# Gas_Analyser_O2_CO2.net
KiCad netlist of a schematic drawn in Altium Designer
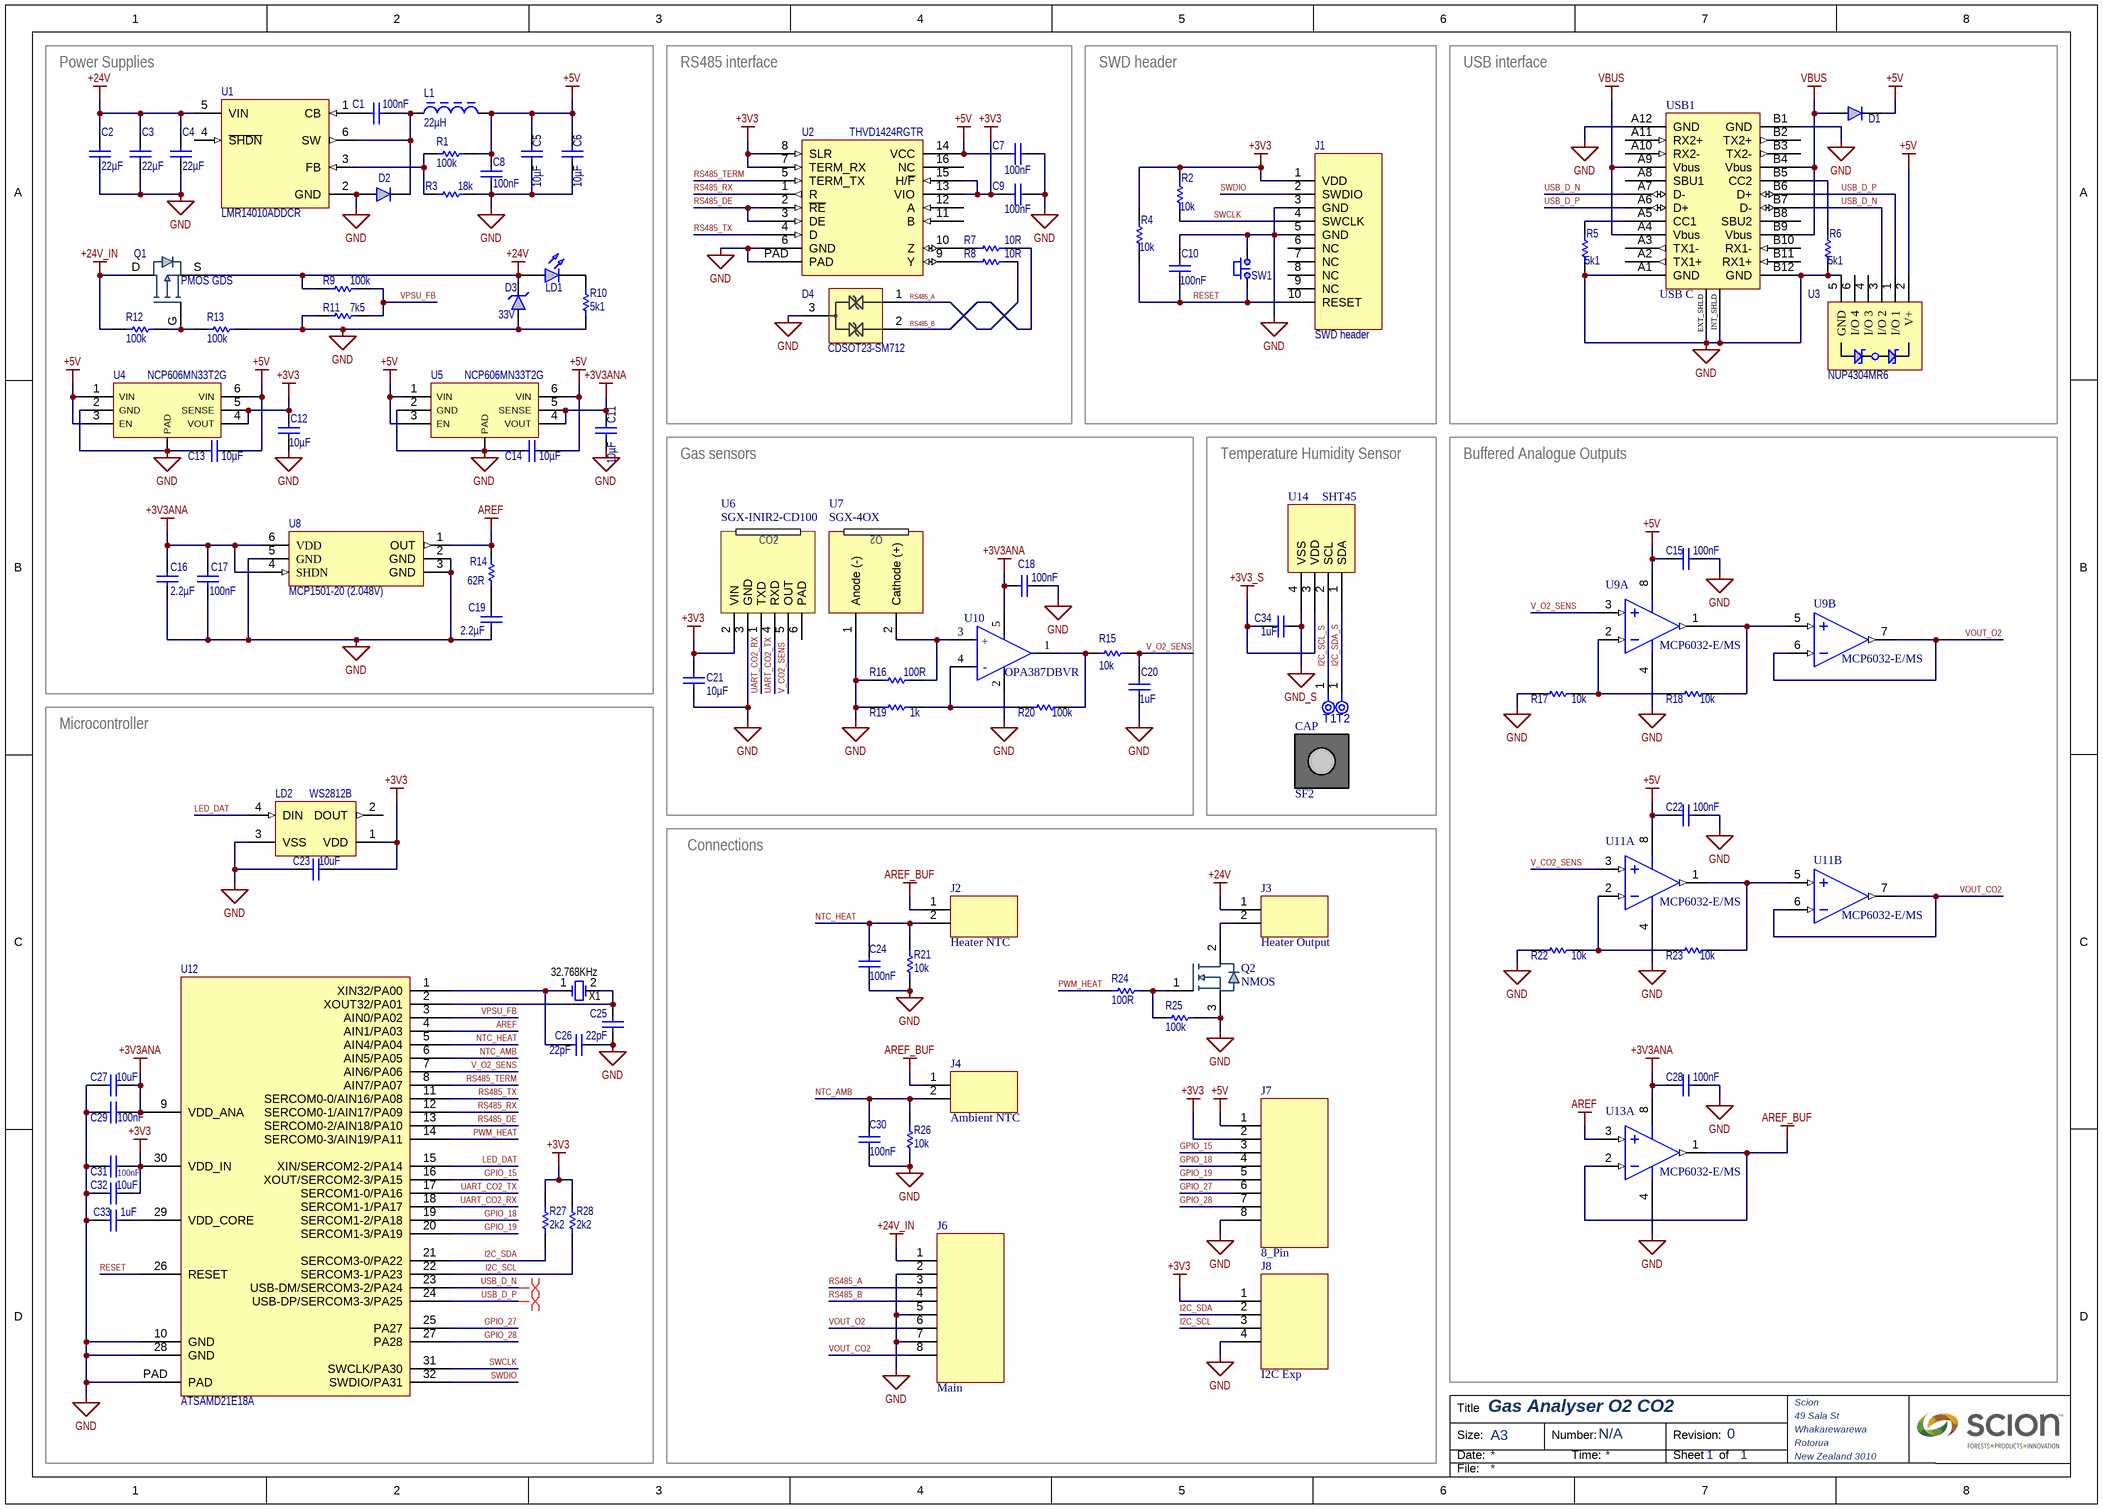
[diagram p0: Gas Analyser O2 CO2.SchDoc]

(export (version "E")
  (design (tool "Eeschema 10.0.6"))
  (components
    (comp (ref "C1")
      (value "100nF")
      (footprint "0603_CAP")
      (description "SMD Capacitor")
      (fields (field (name "Comment") "Capacitor"))
      (libsource (lib "Scion Research") (part "CMP-019-00005-2"))
    )
    (comp (ref "C2")
      (value "22µF")
      (footprint "1206_CAP")
      (description "SMD Capacitor")
      (fields (field (name "Comment") "Capacitor"))
      (libsource (lib "Scion Research") (part "CMP-019-00005-2"))
    )
    (comp (ref "C3")
      (value "22µF")
      (footprint "1206_CAP")
      (description "SMD Capacitor")
      (fields (field (name "Comment") "Capacitor"))
      (libsource (lib "Scion Research") (part "CMP-019-00005-2"))
    )
    (comp (ref "C4")
      (value "22µF")
      (footprint "1206_CAP")
      (description "SMD Capacitor")
      (fields (field (name "Comment") "Capacitor"))
      (libsource (lib "Scion Research") (part "CMP-019-00005-2"))
    )
    (comp (ref "C5")
      (value "10µF")
      (footprint "0603_CAP")
      (description "SMD Capacitor")
      (fields (field (name "Comment") "Capacitor"))
      (libsource (lib "Scion Research") (part "CMP-019-00005-2"))
    )
    (comp (ref "C6")
      (value "10µF")
      (footprint "0603_CAP")
      (description "SMD Capacitor")
      (fields (field (name "Comment") "Capacitor"))
      (libsource (lib "Scion Research") (part "CMP-019-00005-2"))
    )
    (comp (ref "C7")
      (value "100nF")
      (footprint "0603_CAP")
      (description "SMD Capacitor")
      (fields (field (name "Comment") "Capacitor"))
      (libsource (lib "Scion Research") (part "CMP-019-00005-2"))
    )
    (comp (ref "C8")
      (value "100nF")
      (footprint "0603_CAP")
      (description "SMD Capacitor")
      (fields (field (name "Comment") "Capacitor"))
      (libsource (lib "Scion Research") (part "CMP-019-00005-2"))
    )
    (comp (ref "C9")
      (value "100nF")
      (footprint "0603_CAP")
      (description "SMD Capacitor")
      (fields (field (name "Comment") "Capacitor"))
      (libsource (lib "Scion Research") (part "CMP-019-00005-2"))
    )
    (comp (ref "C10")
      (value "100nF")
      (footprint "0603_CAP")
      (description "SMD Capacitor")
      (fields (field (name "Comment") "Capacitor"))
      (libsource (lib "Scion Research") (part "CMP-019-00005-2"))
    )
    (comp (ref "C11")
      (value "10µF")
      (footprint "0603_CAP")
      (description "SMD Capacitor")
      (fields (field (name "Comment") "Capacitor"))
      (libsource (lib "Scion Research") (part "CMP-019-00005-2"))
    )
    (comp (ref "C12")
      (value "10µF")
      (footprint "0603_CAP")
      (description "SMD Capacitor")
      (fields (field (name "Comment") "Capacitor"))
      (libsource (lib "Scion Research") (part "CMP-019-00005-2"))
    )
    (comp (ref "C13")
      (value "10µF")
      (footprint "0603_CAP")
      (description "SMD Capacitor")
      (fields (field (name "Comment") "Capacitor"))
      (libsource (lib "Scion Research") (part "CMP-019-00005-2"))
    )
    (comp (ref "C14")
      (value "10µF")
      (footprint "0603_CAP")
      (description "SMD Capacitor")
      (fields (field (name "Comment") "Capacitor"))
      (libsource (lib "Scion Research") (part "CMP-019-00005-2"))
    )
    (comp (ref "C15")
      (value "100nF")
      (footprint "0603_CAP")
      (description "SMD Capacitor")
      (fields (field (name "Comment") "Capacitor"))
      (libsource (lib "Scion Research") (part "CMP-019-00005-2"))
    )
    (comp (ref "C16")
      (value "2.2µF")
      (footprint "0603_CAP")
      (description "SMD Capacitor")
      (fields (field (name "Comment") "Capacitor"))
      (libsource (lib "Scion Research") (part "CMP-019-00005-2"))
    )
    (comp (ref "C17")
      (value "100nF")
      (footprint "0603_CAP")
      (description "SMD Capacitor")
      (fields (field (name "Comment") "Capacitor"))
      (libsource (lib "Scion Research") (part "CMP-019-00005-2"))
    )
    (comp (ref "C18")
      (value "100nF")
      (footprint "0603_CAP")
      (description "SMD Capacitor")
      (fields (field (name "Comment") "Capacitor"))
      (libsource (lib "Scion Research") (part "CMP-019-00005-2"))
    )
    (comp (ref "C19")
      (value "2.2µF")
      (footprint "0603_CAP")
      (description "SMD Capacitor")
      (fields (field (name "Comment") "Capacitor"))
      (libsource (lib "Scion Research") (part "CMP-019-00005-2"))
    )
    (comp (ref "C20")
      (value "1uF")
      (footprint "0603_CAP")
      (description "SMD Capacitor")
      (fields (field (name "Comment") "Capacitor"))
      (libsource (lib "Scion Research") (part "CMP-019-00005-2"))
    )
    (comp (ref "C21")
      (value "10µF")
      (footprint "0603_CAP")
      (description "SMD Capacitor")
      (fields (field (name "Comment") "Capacitor"))
      (libsource (lib "Scion Research") (part "CMP-019-00005-2"))
    )
    (comp (ref "C22")
      (value "100nF")
      (footprint "0603_CAP")
      (description "SMD Capacitor")
      (fields (field (name "Comment") "Capacitor"))
      (libsource (lib "Scion Research") (part "CMP-019-00005-2"))
    )
    (comp (ref "C23")
      (value "10uF")
      (footprint "0603_CAP")
      (description "SMD Capacitor")
      (fields (field (name "Comment") "Capacitor"))
      (libsource (lib "Scion Research") (part "CMP-019-00005-2"))
    )
    (comp (ref "C24")
      (value "100nF")
      (footprint "0603_CAP")
      (description "SMD Capacitor")
      (fields (field (name "Comment") "Capacitor"))
      (libsource (lib "Scion Research") (part "CMP-019-00005-2"))
    )
    (comp (ref "C25")
      (value "22pF")
      (footprint "0402_CAP")
      (description "SMD Capacitor")
      (fields (field (name "Comment") "Capacitor"))
      (libsource (lib "Scion Research") (part "CMP-019-00005-2"))
    )
    (comp (ref "C26")
      (value "22pF")
      (footprint "0402_CAP")
      (description "SMD Capacitor")
      (fields (field (name "Comment") "Capacitor"))
      (libsource (lib "Scion Research") (part "CMP-019-00005-2"))
    )
    (comp (ref "C27")
      (value "10uF")
      (footprint "0603_CAP")
      (description "SMD Capacitor")
      (fields (field (name "Comment") "Capacitor"))
      (libsource (lib "Scion Research") (part "CMP-019-00005-2"))
    )
    (comp (ref "C28")
      (value "100nF")
      (footprint "0603_CAP")
      (description "SMD Capacitor")
      (fields (field (name "Comment") "Capacitor"))
      (libsource (lib "Scion Research") (part "CMP-019-00005-2"))
    )
    (comp (ref "C29")
      (value "100nF")
      (footprint "0402_CAP")
      (description "SMD Capacitor")
      (fields (field (name "Comment") "Capacitor"))
      (libsource (lib "Scion Research") (part "CMP-019-00005-2"))
    )
    (comp (ref "C30")
      (value "100nF")
      (footprint "0603_CAP")
      (description "SMD Capacitor")
      (fields (field (name "Comment") "Capacitor"))
      (libsource (lib "Scion Research") (part "CMP-019-00005-2"))
    )
    (comp (ref "C31")
      (value "100nF")
      (footprint "0402_CAP")
      (description "SMD Capacitor")
      (fields (field (name "Comment") "Capacitor"))
      (libsource (lib "Scion Research") (part "CMP-019-00005-2"))
    )
    (comp (ref "C32")
      (value "10uF")
      (footprint "0603_CAP")
      (description "SMD Capacitor")
      (fields (field (name "Comment") "Capacitor"))
      (libsource (lib "Scion Research") (part "CMP-019-00005-2"))
    )
    (comp (ref "C33")
      (value "1uF")
      (footprint "0402_CAP")
      (description "SMD Capacitor")
      (fields (field (name "Comment") "Capacitor"))
      (libsource (lib "Scion Research") (part "CMP-019-00005-2"))
    )
    (comp (ref "C34")
      (value "1uF")
      (footprint "0603_CAP")
      (description "SMD Capacitor")
      (fields (field (name "Comment") "Capacitor"))
      (libsource (lib "Scion Research") (part "CMP-019-00005-2"))
    )
    (comp (ref "CAP")
      (value "SF2")
      (footprint "SF2-Footprint-1")
      (description "Sensirion SHT cap for SHT4x sensors")
      (libsource (lib "Scion Research") (part "SF2-Symbol-1"))
    )
    (comp (ref "D1")
      (value "Diode")
      (footprint "SOD-123")
      (description "SMD Diode")
      (libsource (lib "Scion Research") (part "Diode"))
    )
    (comp (ref "D2")
      (value "Diode")
      (footprint "SOD-123")
      (description "SMD Diode")
      (libsource (lib "Scion Research") (part "Diode"))
    )
    (comp (ref "D3")
      (value "Transil")
      (footprint "SMBJ")
      (description "Transient Voltage Suppressor")
      (fields (field (name "RATED VOLTAGE") "33V"))
      (libsource (lib "Scion Research") (part "CMP-004-0042-1"))
    )
    (comp (ref "D4")
      (value "CDSOT23-SM712")
      (footprint "FP-SOT23-IPC_C")
      (description "Trans Voltage Suppressor Diode, 400W, 7V V(RWM), Bidirectional, 2 Element, Silicon")
      (libsource (lib "Scion Research") (part "CDSOT23-SM712"))
    )
    (comp (ref "J1")
      (value "SWD header")
      (footprint "DIP10_1.27_M_SMD")
      (description "10 Pin Connector")
      (libsource (lib "Scion Research") (part "CMP-002-00071-2"))
    )
    (comp (ref "J2")
      (value "Heater NTC")
      (footprint "2mm RA S2B-PH-K-S")
      (description "2 Pin Connector")
      (libsource (lib "Scion Research") (part "CMP-002-00074-8"))
    )
    (comp (ref "J3")
      (value "Heater Output")
      (footprint "2mm RA S2B-PH-K-S")
      (description "2 Pin Connector")
      (libsource (lib "Scion Research") (part "CMP-002-00074-8"))
    )
    (comp (ref "J4")
      (value "Ambient NTC")
      (footprint "2mm RA S2B-PH-K-S")
      (description "2 Pin Connector")
      (libsource (lib "Scion Research") (part "CMP-002-00074-8"))
    )
    (comp (ref "J6")
      (value "Main")
      (footprint "8P RA MOLEX Clik-MATE 1.5mm")
      (description "8 Pin Connector")
      (libsource (lib "Scion Research") (part "CMP-002-00084-5"))
    )
    (comp (ref "J7")
      (value "8_Pin")
      (footprint "8P DIP Male Header 2.54mm")
      (description "8 Pin Connector")
      (libsource (lib "Scion Research") (part "CMP-002-00084-5"))
    )
    (comp (ref "J8")
      (value "I2C Exp")
      (footprint "4P RA MOLEX Clik-MATE 1.5mm")
      (description "4 Pin Connector")
      (libsource (lib "Scion Research") (part "CMP-002-00078-6"))
    )
    (comp (ref "L1")
      (value "22µH")
      (footprint "BOUR-SRN8040_V")
      (description "Power Inductor")
      (fields (field (name "Comment") "Inductor"))
      (libsource (lib "Scion Research") (part "Inductor"))
    )
    (comp (ref "LD1")
      (value "LED")
      (footprint "0805")
      (description "SMD LED")
      (libsource (lib "Scion Research") (part "CMP-004-00032-1"))
    )
    (comp (ref "LD2")
      (value "WS2812B")
      (footprint "WS2812B-2020")
      (fields (field (name "MANUFACTURER") "Adafruit Industries"))
      (libsource (lib "Scion Research") (part "CMP-007-00035-3"))
    )
    (comp (ref "Q1")
      (value "PMOS GDS")
      (footprint "PowerDI 5060-8")
      (description "P Channel MOSFET")
      (libsource (lib "Scion Research") (part "CMP-004-0035-2"))
    )
    (comp (ref "Q2")
      (value "NMOS")
      (footprint "SOT-23")
      (description "N Channel MOSFET")
      (libsource (lib "Scion Research") (part "CMP-004-0025-1"))
    )
    (comp (ref "R1")
      (value "Resistor")
      (footprint "0603_RES")
      (description "SMD Resistor")
      (fields (field (name "ALTIUM_VALUE") "100k"))
      (libsource (lib "Scion Research") (part "CMP-009-00177-2"))
    )
    (comp (ref "R2")
      (value "Resistor")
      (footprint "0603_RES")
      (description "SMD Resistor")
      (fields (field (name "ALTIUM_VALUE") "10k"))
      (libsource (lib "Scion Research") (part "CMP-009-00177-2"))
    )
    (comp (ref "R3")
      (value "Resistor")
      (footprint "0603_RES")
      (description "SMD Resistor")
      (fields (field (name "ALTIUM_VALUE") "18k"))
      (libsource (lib "Scion Research") (part "CMP-009-00177-2"))
    )
    (comp (ref "R4")
      (value "Resistor")
      (footprint "0603_RES")
      (description "SMD Resistor")
      (fields (field (name "ALTIUM_VALUE") "10k"))
      (libsource (lib "Scion Research") (part "CMP-009-00177-2"))
    )
    (comp (ref "R5")
      (value "Resistor")
      (footprint "0603_RES")
      (description "SMD Resistor")
      (fields (field (name "ALTIUM_VALUE") "5k1"))
      (libsource (lib "Scion Research") (part "CMP-009-00177-2"))
    )
    (comp (ref "R6")
      (value "Resistor")
      (footprint "0603_RES")
      (description "SMD Resistor")
      (fields (field (name "ALTIUM_VALUE") "5k1"))
      (libsource (lib "Scion Research") (part "CMP-009-00177-2"))
    )
    (comp (ref "R7")
      (value "Resistor")
      (footprint "0603_RES")
      (description "SMD Resistor")
      (fields (field (name "ALTIUM_VALUE") "10R"))
      (libsource (lib "Scion Research") (part "CMP-009-00177-2"))
    )
    (comp (ref "R8")
      (value "Resistor")
      (footprint "0603_RES")
      (description "SMD Resistor")
      (fields (field (name "ALTIUM_VALUE") "10R"))
      (libsource (lib "Scion Research") (part "CMP-009-00177-2"))
    )
    (comp (ref "R9")
      (value "Resistor")
      (footprint "0603_RES")
      (description "SMD Resistor")
      (fields (field (name "ALTIUM_VALUE") "100k"))
      (libsource (lib "Scion Research") (part "CMP-009-00177-2"))
    )
    (comp (ref "R10")
      (value "Resistor")
      (footprint "0603_RES")
      (description "SMD Resistor")
      (fields (field (name "ALTIUM_VALUE") "5k1"))
      (libsource (lib "Scion Research") (part "CMP-009-00177-2"))
    )
    (comp (ref "R11")
      (value "Resistor")
      (footprint "0603_RES")
      (description "SMD Resistor")
      (fields (field (name "ALTIUM_VALUE") "7k5"))
      (libsource (lib "Scion Research") (part "CMP-009-00177-2"))
    )
    (comp (ref "R12")
      (value "Resistor")
      (footprint "0603_RES")
      (description "SMD Resistor")
      (fields (field (name "ALTIUM_VALUE") "100k"))
      (libsource (lib "Scion Research") (part "CMP-009-00177-2"))
    )
    (comp (ref "R13")
      (value "Resistor")
      (footprint "0603_RES")
      (description "SMD Resistor")
      (fields (field (name "ALTIUM_VALUE") "100k"))
      (libsource (lib "Scion Research") (part "CMP-009-00177-2"))
    )
    (comp (ref "R14")
      (value "Resistor")
      (footprint "0603_RES")
      (description "SMD Resistor")
      (fields (field (name "ALTIUM_VALUE") "62R"))
      (libsource (lib "Scion Research") (part "CMP-009-00177-2"))
    )
    (comp (ref "R15")
      (value "Resistor")
      (footprint "0603_RES")
      (description "SMD Resistor")
      (fields (field (name "ALTIUM_VALUE") "10k"))
      (libsource (lib "Scion Research") (part "CMP-009-00177-2"))
    )
    (comp (ref "R16")
      (value "Resistor")
      (footprint "0603_RES")
      (description "SMD Resistor")
      (fields (field (name "ALTIUM_VALUE") "100R"))
      (libsource (lib "Scion Research") (part "CMP-009-00177-2"))
    )
    (comp (ref "R17")
      (value "Resistor")
      (footprint "0603_RES")
      (description "SMD Resistor")
      (fields (field (name "ALTIUM_VALUE") "10k"))
      (libsource (lib "Scion Research") (part "CMP-009-00177-2"))
    )
    (comp (ref "R18")
      (value "Resistor")
      (footprint "0603_RES")
      (description "SMD Resistor")
      (fields (field (name "ALTIUM_VALUE") "10k"))
      (libsource (lib "Scion Research") (part "CMP-009-00177-2"))
    )
    (comp (ref "R19")
      (value "Resistor")
      (footprint "0603_RES")
      (description "SMD Resistor")
      (fields (field (name "ALTIUM_VALUE") "1k"))
      (libsource (lib "Scion Research") (part "CMP-009-00177-2"))
    )
    (comp (ref "R20")
      (value "Resistor")
      (footprint "0603_RES")
      (description "SMD Resistor")
      (fields (field (name "ALTIUM_VALUE") "100k"))
      (libsource (lib "Scion Research") (part "CMP-009-00177-2"))
    )
    (comp (ref "R21")
      (value "Resistor")
      (footprint "0603_RES")
      (description "SMD Resistor")
      (fields (field (name "ALTIUM_VALUE") "10k"))
      (libsource (lib "Scion Research") (part "CMP-009-00177-2"))
    )
    (comp (ref "R22")
      (value "Resistor")
      (footprint "0603_RES")
      (description "SMD Resistor")
      (fields (field (name "ALTIUM_VALUE") "10k"))
      (libsource (lib "Scion Research") (part "CMP-009-00177-2"))
    )
    (comp (ref "R23")
      (value "Resistor")
      (footprint "0603_RES")
      (description "SMD Resistor")
      (fields (field (name "ALTIUM_VALUE") "10k"))
      (libsource (lib "Scion Research") (part "CMP-009-00177-2"))
    )
    (comp (ref "R24")
      (value "Resistor")
      (footprint "0603_RES")
      (description "SMD Resistor")
      (fields (field (name "ALTIUM_VALUE") "100R"))
      (libsource (lib "Scion Research") (part "CMP-009-00177-2"))
    )
    (comp (ref "R25")
      (value "Resistor")
      (footprint "0603_RES")
      (description "SMD Resistor")
      (fields (field (name "ALTIUM_VALUE") "100k"))
      (libsource (lib "Scion Research") (part "CMP-009-00177-2"))
    )
    (comp (ref "R26")
      (value "Resistor")
      (footprint "0603_RES")
      (description "SMD Resistor")
      (fields (field (name "ALTIUM_VALUE") "10k"))
      (libsource (lib "Scion Research") (part "CMP-009-00177-2"))
    )
    (comp (ref "R27")
      (value "Resistor")
      (footprint "0603_RES")
      (description "SMD Resistor")
      (fields (field (name "ALTIUM_VALUE") "2k2"))
      (libsource (lib "Scion Research") (part "CMP-009-00177-2"))
    )
    (comp (ref "R28")
      (value "Resistor")
      (footprint "0603_RES")
      (description "SMD Resistor")
      (fields (field (name "ALTIUM_VALUE") "2k2"))
      (libsource (lib "Scion Research") (part "CMP-009-00177-2"))
    )
    (comp (ref "SW1")
      (value "EVP-AAN02Q")
      (footprint "FP-EVP-AAN02Q-MFG")
      (description "Switch Tactile N.O. SPST Rectangular Button J-Bend 0.02A 15VDC 100000Cycles 5N SMD T/R")
      (libsource (lib "Scion Research") (part "67890d47754ac483cb1d3ba3be74b6c"))
    )
    (comp (ref "T1")
      (value "Test Point")
      (footprint "TP06R")
      (description "0.6mm round")
      (libsource (lib "Scion Research") (part "CMP-00028-00002-1"))
    )
    (comp (ref "T2")
      (value "Test Point")
      (footprint "TP06R")
      (description "0.6mm round")
      (libsource (lib "Scion Research") (part "CMP-00028-00002-1"))
    )
    (comp (ref "U1")
      (value "LMR14010ADDCR")
      (footprint "FP-DDC0006A-IPC_A")
      (description "7-40VDC-DC buck converter")
      (libsource (lib "Scion Research") (part "LMR14010"))
    )
    (comp (ref "U2")
      (value "THVD1424RGTR")
      (footprint "QFN50P300X300X100_HS-17N")
      (libsource (lib "Scion Research") (part "THVD1424RGTR-Symbol-1"))
    )
    (comp (ref "U3")
      (value "NUP4304MR6")
      (footprint "TSOP-6")
      (description "ESD Protection Doide Array")
      (libsource (lib "Scion Research") (part "CMP-004-0028-1"))
    )
    (comp (ref "U4")
      (value "NCP606MN33T2G")
      (footprint "QFN95P330X295X100_HS-7N")
      (description "Fixed Positive LDO Regulator, 3.3V, 0.22V Dropout, CMOS")
      (libsource (lib "Scion Research") (part "NCP606MN33T2G-Symbol-1"))
    )
    (comp (ref "U5")
      (value "NCP606MN33T2G")
      (footprint "QFN95P330X295X100_HS-7N")
      (description "Fixed Positive LDO Regulator, 3.3V, 0.22V Dropout, CMOS")
      (libsource (lib "Scion Research") (part "NCP606MN33T2G-Symbol-1"))
    )
    (comp (ref "U6")
      (value "SGX-INIR2-CD100")
      (footprint "SGX-INIR2-CD100-Footprint-1")
      (description "SGX Sensortech IR CO2 Sensor Module")
      (libsource (lib "Scion Research") (part "SGX-INIR2-CD100"))
    )
    (comp (ref "U7")
      (value "SGX-4OX")
      (footprint "SGX-4OX-Footprint-1")
      (description "SGX Sensortech Electrochemical O2 Sensor Module")
      (libsource (lib "Scion Research") (part "SGX-4OX"))
    )
    (comp (ref "U8")
      (value "MCP1501-20 (2.048V)")
      (footprint "SOT-6")
      (description "Voltage Reference")
      (libsource (lib "Scion Research") (part "CMP-004-0020-1"))
    )
    (comp (ref "U9")
      (value "MCP6032-E/MS")
      (footprint "MSOP-MS8_M")
      (description "Op Amp Dual Precision Amplifier R-R I/O 5.5V Automotive 8-Pin MSOP Tube")
      (libsource (lib "Scion Research") (part "AMP-OPA-MCP6032-IL8"))
    )
    (comp (ref "U10")
      (value "OPA387DBVR")
      (footprint "FP-DBV0005A-IPC_A")
      (libsource (lib "Scion Research") (part "1dcd28e651784f0a5a8ed6f8452eeff"))
    )
    (comp (ref "U11")
      (value "MCP6032-E/MS")
      (footprint "MSOP-MS8_M")
      (description "Op Amp Dual Precision Amplifier R-R I/O 5.5V Automotive 8-Pin MSOP Tube")
      (libsource (lib "Scion Research") (part "AMP-OPA-MCP6032-IL8"))
    )
    (comp (ref "U12")
      (value "ATSAMD21E18A")
      (footprint "32P QFN")
      (libsource (lib "Scion Research") (part "CMP-00013-1"))
    )
    (comp (ref "U13")
      (value "MCP6032-E/MS")
      (footprint "MSOP-MS8_M")
      (description "Op Amp Dual Precision Amplifier R-R I/O 5.5V Automotive 8-Pin MSOP Tube")
      (libsource (lib "Scion Research") (part "AMP-OPA-MCP6032-IL8"))
    )
    (comp (ref "U14")
      (value "SHT45")
      (footprint "SHT45-AD1B-R3-Footprint-1")
      (libsource (lib "Scion Research") (part "CMP-00047-1"))
    )
    (comp (ref "USB1")
      (value "USB C")
      (footprint "GT-USB-7010ASV")
      (description "Vertical or RA Type C Usb Connector Rohs Compliant: Yes")
      (libsource (lib "Scion Research") (part "CMP-00005-5"))
    )
    (comp (ref "X1")
      (value "32.768KHz")
      (footprint "ABRA-ABS07-2_V")
      (fields (field (name "TOLERANCE") "20ppm") (field (name "MANUFACTURER") "Abracon"))
      (libsource (lib "Scion Research") (part "CMP-003-00022-1"))
    )
  )
  (nets
    (net (code "1") (name "+3V3") (class "Default")
      (node (ref "C12") (pin "1") (pinfunction "1_1") (pintype "passive"))
      (node (ref "C21") (pin "1") (pinfunction "1_1") (pintype "passive"))
      (node (ref "C23") (pin "1") (pinfunction "1_1") (pintype "passive"))
      (node (ref "C31") (pin "1") (pinfunction "1_1") (pintype "passive"))
      (node (ref "C32") (pin "1") (pinfunction "1_1") (pintype "passive"))
      (node (ref "C9") (pin "2") (pinfunction "2_2") (pintype "passive"))
      (node (ref "J1") (pin "1") (pinfunction "VDD_1") (pintype "passive"))
      (node (ref "J7") (pin "2") (pinfunction "2_2") (pintype "passive"))
      (node (ref "J8") (pin "1") (pinfunction "1_1") (pintype "passive"))
      (node (ref "LD2") (pin "1") (pinfunction "VDD_1") (pintype "power_in"))
      (node (ref "R2") (pin "1") (pinfunction "1_1") (pintype "passive"))
      (node (ref "R27") (pin "2") (pinfunction "2_2") (pintype "passive"))
      (node (ref "R28") (pin "2") (pinfunction "2_2") (pintype "passive"))
      (node (ref "R4") (pin "1") (pinfunction "1_1") (pintype "passive"))
      (node (ref "U12") (pin "30") (pinfunction "VDD_IN_30") (pintype "passive"))
      (node (ref "U2") (pin "13") (pinfunction "VIO_13") (pintype "power_in"))
      (node (ref "U2") (pin "15") (pinfunction "H/~{F}_15") (pintype "input"))
      (node (ref "U2") (pin "7") (pinfunction "TERM_RX_7") (pintype "input"))
      (node (ref "U2") (pin "8") (pinfunction "SLR_8") (pintype "input"))
      (node (ref "U4") (pin "4") (pinfunction "VOUT_4") (pintype "passive"))
      (node (ref "U4") (pin "5") (pinfunction "SENSE_5") (pintype "passive"))
      (node (ref "U6") (pin "2") (pinfunction "VIN_2") (pintype "passive"))
    )
    (net (code "2") (name "+3V3ANA") (class "Default")
      (node (ref "C11") (pin "1") (pinfunction "1_1") (pintype "passive"))
      (node (ref "C16") (pin "1") (pinfunction "1_1") (pintype "passive"))
      (node (ref "C17") (pin "1") (pinfunction "1_1") (pintype "passive"))
      (node (ref "C18") (pin "1") (pinfunction "1_1") (pintype "passive"))
      (node (ref "C27") (pin "1") (pinfunction "1_1") (pintype "passive"))
      (node (ref "C28") (pin "1") (pinfunction "1_1") (pintype "passive"))
      (node (ref "C29") (pin "1") (pinfunction "1_1") (pintype "passive"))
      (node (ref "U10") (pin "5") (pinfunction "V+_5") (pintype "power_in"))
      (node (ref "U12") (pin "9") (pinfunction "VDD_ANA_9") (pintype "passive"))
      (node (ref "U13") (pin "8") (pinfunction "V+_8") (pintype "passive"))
      (node (ref "U5") (pin "4") (pinfunction "VOUT_4") (pintype "passive"))
      (node (ref "U5") (pin "5") (pinfunction "SENSE_5") (pintype "passive"))
      (node (ref "U8") (pin "4") (pinfunction "SHDN_4") (pintype "input"))
      (node (ref "U8") (pin "6") (pinfunction "VDD_6") (pintype "power_in"))
    )
    (net (code "3") (name "+3V3_S") (class "Default")
      (node (ref "C34") (pin "2") (pinfunction "2_2") (pintype "passive"))
      (node (ref "U14") (pin "3") (pinfunction "VDD_3") (pintype "passive"))
    )
    (net (code "4") (name "+5V") (class "Default")
      (node (ref "C13") (pin "1") (pinfunction "1_1") (pintype "passive"))
      (node (ref "C14") (pin "1") (pinfunction "1_1") (pintype "passive"))
      (node (ref "C15") (pin "1") (pinfunction "1_1") (pintype "passive"))
      (node (ref "C22") (pin "1") (pinfunction "1_1") (pintype "passive"))
      (node (ref "C5") (pin "1") (pinfunction "1_1") (pintype "passive"))
      (node (ref "C6") (pin "1") (pinfunction "1_1") (pintype "passive"))
      (node (ref "C7") (pin "2") (pinfunction "2_2") (pintype "passive"))
      (node (ref "C8") (pin "1") (pinfunction "1_1") (pintype "passive"))
      (node (ref "D1") (pin "1") (pinfunction "K_1") (pintype "passive"))
      (node (ref "J7") (pin "1") (pinfunction "1_1") (pintype "passive"))
      (node (ref "L1") (pin "2") (pinfunction "2_2") (pintype "passive"))
      (node (ref "R1") (pin "2") (pinfunction "2_2") (pintype "passive"))
      (node (ref "U11") (pin "8") (pinfunction "V+_8") (pintype "passive"))
      (node (ref "U2") (pin "14") (pinfunction "VCC_14") (pintype "power_in"))
      (node (ref "U3") (pin "2") (pinfunction "V+_2") (pintype "power_in"))
      (node (ref "U4") (pin "1") (pinfunction "VIN_1") (pintype "passive"))
      (node (ref "U4") (pin "3") (pinfunction "EN_3") (pintype "passive"))
      (node (ref "U4") (pin "6") (pinfunction "VIN_6") (pintype "passive"))
      (node (ref "U5") (pin "1") (pinfunction "VIN_1") (pintype "passive"))
      (node (ref "U5") (pin "3") (pinfunction "EN_3") (pintype "passive"))
      (node (ref "U5") (pin "6") (pinfunction "VIN_6") (pintype "passive"))
      (node (ref "U9") (pin "8") (pinfunction "V+_8") (pintype "passive"))
    )
    (net (code "5") (name "+24V") (class "Default")
      (node (ref "C2") (pin "1") (pinfunction "1_1") (pintype "passive"))
      (node (ref "C3") (pin "1") (pinfunction "1_1") (pintype "passive"))
      (node (ref "C4") (pin "1") (pinfunction "1_1") (pintype "passive"))
      (node (ref "D3") (pin "2") (pinfunction "K_2") (pintype "passive"))
      (node (ref "J3") (pin "1") (pinfunction "+_1") (pintype "passive"))
      (node (ref "LD1") (pin "2") (pinfunction "A_2") (pintype "passive"))
      (node (ref "Q1") (pin "S") (pinfunction "S_S") (pintype "passive"))
      (node (ref "R9") (pin "1") (pinfunction "1_1") (pintype "passive"))
      (node (ref "U1") (pin "5") (pinfunction "VIN_5") (pintype "power_in"))
    )
    (net (code "6") (name "+24V_IN") (class "Default")
      (node (ref "J6") (pin "1") (pinfunction "1_1") (pintype "passive"))
      (node (ref "Q1") (pin "D") (pinfunction "D_D") (pintype "passive"))
      (node (ref "R12") (pin "1") (pinfunction "1_1") (pintype "passive"))
    )
    (net (code "7") (name "/GPIO_15") (class "Default")
      (node (ref "J7") (pin "3") (pinfunction "3_3") (pintype "passive"))
      (node (ref "U12") (pin "16") (pinfunction "XOUT/SERCOM2-3/PA15_16") (pintype "passive"))
    )
    (net (code "8") (name "/GPIO_18") (class "Default")
      (node (ref "J7") (pin "4") (pinfunction "4_4") (pintype "passive"))
      (node (ref "U12") (pin "19") (pinfunction "SERCOM1-2/PA18_19") (pintype "passive"))
    )
    (net (code "9") (name "/GPIO_19") (class "Default")
      (node (ref "J7") (pin "5") (pinfunction "5_5") (pintype "passive"))
      (node (ref "U12") (pin "20") (pinfunction "SERCOM1-3/PA19_20") (pintype "passive"))
    )
    (net (code "10") (name "/GPIO_27") (class "Default")
      (node (ref "J7") (pin "6") (pinfunction "6_6") (pintype "passive"))
      (node (ref "U12") (pin "25") (pinfunction "PA27_25") (pintype "passive"))
    )
    (net (code "11") (name "/GPIO_28") (class "Default")
      (node (ref "J7") (pin "7") (pinfunction "7_7") (pintype "passive"))
      (node (ref "U12") (pin "27") (pinfunction "PA28_27") (pintype "passive"))
    )
    (net (code "12") (name "/I2C_SCL") (class "Default")
      (node (ref "J8") (pin "3") (pinfunction "3_3") (pintype "passive"))
      (node (ref "R28") (pin "1") (pinfunction "1_1") (pintype "passive"))
      (node (ref "U12") (pin "22") (pinfunction "SERCOM3-1/PA23_22") (pintype "passive"))
    )
    (net (code "13") (name "/I2C_SCL_S") (class "Default")
      (node (ref "T1") (pin "1") (pinfunction "TP_1") (pintype "passive"))
      (node (ref "U14") (pin "2") (pinfunction "SCL_2") (pintype "passive"))
    )
    (net (code "14") (name "/I2C_SDA") (class "Default")
      (node (ref "J8") (pin "2") (pinfunction "2_2") (pintype "passive"))
      (node (ref "R27") (pin "1") (pinfunction "1_1") (pintype "passive"))
      (node (ref "U12") (pin "21") (pinfunction "SERCOM3-0/PA22_21") (pintype "passive"))
    )
    (net (code "15") (name "/I2C_SDA_S") (class "Default")
      (node (ref "T2") (pin "1") (pinfunction "TP_1") (pintype "passive"))
      (node (ref "U14") (pin "1") (pinfunction "SDA_1") (pintype "passive"))
    )
    (net (code "16") (name "/LED_DAT") (class "Default")
      (node (ref "LD2") (pin "4") (pinfunction "DIN_4") (pintype "input"))
      (node (ref "U12") (pin "15") (pinfunction "XIN/SERCOM2-2/PA14_15") (pintype "passive"))
    )
    (net (code "17") (name "/NTC_AMB") (class "Default")
      (node (ref "C30") (pin "2") (pinfunction "2_2") (pintype "passive"))
      (node (ref "J4") (pin "2") (pinfunction "-_2") (pintype "passive"))
      (node (ref "R26") (pin "2") (pinfunction "2_2") (pintype "passive"))
      (node (ref "U12") (pin "6") (pinfunction "AIN5/PA05_6") (pintype "passive"))
    )
    (net (code "18") (name "/NTC_HEAT") (class "Default")
      (node (ref "C24") (pin "2") (pinfunction "2_2") (pintype "passive"))
      (node (ref "J2") (pin "2") (pinfunction "-_2") (pintype "passive"))
      (node (ref "R21") (pin "2") (pinfunction "2_2") (pintype "passive"))
      (node (ref "U12") (pin "5") (pinfunction "AIN4/PA04_5") (pintype "passive"))
    )
    (net (code "19") (name "/PWM_HEAT") (class "Default")
      (node (ref "R24") (pin "2") (pinfunction "2_2") (pintype "passive"))
      (node (ref "U12") (pin "14") (pinfunction "SERCOM0-3/AIN19/PA11_14") (pintype "passive"))
    )
    (net (code "20") (name "/RESET") (class "Default")
      (node (ref "C10") (pin "2") (pinfunction "2_2") (pintype "passive"))
      (node (ref "J1") (pin "10") (pinfunction "RESET_10") (pintype "passive"))
      (node (ref "R4") (pin "2") (pinfunction "2_2") (pintype "passive"))
      (node (ref "SW1") (pin "1") (pinfunction "1_1") (pintype "passive"))
      (node (ref "U12") (pin "26") (pinfunction "RESET_26") (pintype "passive"))
    )
    (net (code "21") (name "/RS485_A") (class "Default")
      (node (ref "D4") (pin "1") (pinfunction "1_1") (pintype "passive"))
      (node (ref "J6") (pin "3") (pinfunction "3_3") (pintype "passive"))
      (node (ref "R8") (pin "1") (pinfunction "1_1") (pintype "passive"))
    )
    (net (code "22") (name "/RS485_B") (class "Default")
      (node (ref "D4") (pin "2") (pinfunction "2_2") (pintype "passive"))
      (node (ref "J6") (pin "4") (pinfunction "4_4") (pintype "passive"))
      (node (ref "R7") (pin "2") (pinfunction "2_2") (pintype "passive"))
    )
    (net (code "23") (name "/RS485_DE") (class "Default")
      (node (ref "U12") (pin "13") (pinfunction "SERCOM0-2/AIN18/PA10_13") (pintype "passive"))
      (node (ref "U2") (pin "2") (pinfunction "~{RE}_2") (pintype "input"))
      (node (ref "U2") (pin "3") (pinfunction "DE_3") (pintype "input"))
    )
    (net (code "24") (name "/RS485_RX") (class "Default")
      (node (ref "U12") (pin "12") (pinfunction "SERCOM0-1/AIN17/PA09_12") (pintype "passive"))
      (node (ref "U2") (pin "1") (pinfunction "R_1") (pintype "output"))
    )
    (net (code "25") (name "/RS485_TERM") (class "Default")
      (node (ref "U12") (pin "8") (pinfunction "AIN7/PA07_8") (pintype "passive"))
      (node (ref "U2") (pin "5") (pinfunction "TERM_TX_5") (pintype "input"))
    )
    (net (code "26") (name "/RS485_TX") (class "Default")
      (node (ref "U12") (pin "11") (pinfunction "SERCOM0-0/AIN16/PA08_11") (pintype "passive"))
      (node (ref "U2") (pin "4") (pinfunction "D_4") (pintype "input"))
    )
    (net (code "27") (name "/SWCLK") (class "Default")
      (node (ref "J1") (pin "4") (pinfunction "SWCLK_4") (pintype "passive"))
      (node (ref "R2") (pin "2") (pinfunction "2_2") (pintype "passive"))
      (node (ref "U12") (pin "31") (pinfunction "SWCLK/PA30_31") (pintype "passive"))
    )
    (net (code "28") (name "/SWDIO") (class "Default")
      (node (ref "J1") (pin "2") (pinfunction "SWDIO_2") (pintype "passive"))
      (node (ref "U12") (pin "32") (pinfunction "SWDIO/PA31_32") (pintype "passive"))
    )
    (net (code "29") (name "/UART_CO2_RX") (class "Default")
      (node (ref "U12") (pin "18") (pinfunction "SERCOM1-1/PA17_18") (pintype "passive"))
      (node (ref "U6") (pin "1") (pinfunction "TXD_1") (pintype "passive"))
    )
    (net (code "30") (name "/UART_CO2_TX") (class "Default")
      (node (ref "U12") (pin "17") (pinfunction "SERCOM1-0/PA16_17") (pintype "passive"))
      (node (ref "U6") (pin "4") (pinfunction "RXD_4") (pintype "passive"))
    )
    (net (code "31") (name "/USB_D_N") (class "Default")
      (node (ref "U12") (pin "23") (pinfunction "USB-DM/SERCOM3-2/PA24_23") (pintype "passive"))
      (node (ref "U3") (pin "3") (pinfunction "I/O_2_3") (pintype "power_in"))
      (node (ref "USB1") (pin "A7") (pinfunction "D-_A7") (pintype "bidirectional"))
      (node (ref "USB1") (pin "B7") (pinfunction "D-_B7") (pintype "bidirectional"))
    )
    (net (code "32") (name "/USB_D_P") (class "Default")
      (node (ref "U12") (pin "24") (pinfunction "USB-DP/SERCOM3-3/PA25_24") (pintype "passive"))
      (node (ref "U3") (pin "1") (pinfunction "I/O_1_1") (pintype "power_in"))
      (node (ref "USB1") (pin "A6") (pinfunction "D+_A6") (pintype "bidirectional"))
      (node (ref "USB1") (pin "B6") (pinfunction "D+_B6") (pintype "bidirectional"))
    )
    (net (code "33") (name "/VOUT_CO2") (class "Default")
      (node (ref "J6") (pin "8") (pinfunction "8_8") (pintype "passive"))
      (node (ref "U11") (pin "6") (pinfunction "VINB-_6") (pintype "input"))
      (node (ref "U11") (pin "7") (pinfunction "VOUTB_7") (pintype "output"))
    )
    (net (code "34") (name "/VOUT_O2") (class "Default")
      (node (ref "J6") (pin "6") (pinfunction "6_6") (pintype "passive"))
      (node (ref "U9") (pin "6") (pinfunction "VINB-_6") (pintype "input"))
      (node (ref "U9") (pin "7") (pinfunction "VOUTB_7") (pintype "output"))
    )
    (net (code "35") (name "/VPSU_FB") (class "Default")
      (node (ref "R11") (pin "2") (pinfunction "2_2") (pintype "passive"))
      (node (ref "R9") (pin "2") (pinfunction "2_2") (pintype "passive"))
      (node (ref "U12") (pin "3") (pinfunction "AIN0/PA02_3") (pintype "passive"))
    )
    (net (code "36") (name "/V_CO2_SENS") (class "Default")
      (node (ref "U11") (pin "3") (pinfunction "VINA+_3") (pintype "input"))
      (node (ref "U6") (pin "5") (pinfunction "OUT_5") (pintype "passive"))
    )
    (net (code "37") (name "/V_O2_SENS") (class "Default")
      (node (ref "C20") (pin "1") (pinfunction "1_1") (pintype "passive"))
      (node (ref "R15") (pin "2") (pinfunction "2_2") (pintype "passive"))
      (node (ref "U12") (pin "7") (pinfunction "AIN6/PA06_7") (pintype "passive"))
      (node (ref "U9") (pin "3") (pinfunction "VINA+_3") (pintype "input"))
    )
    (net (code "38") (name "AREF") (class "Default")
      (node (ref "R14") (pin "1") (pinfunction "1_1") (pintype "passive"))
      (node (ref "U12") (pin "4") (pinfunction "AIN1/PA03_4") (pintype "passive"))
      (node (ref "U13") (pin "3") (pinfunction "VINA+_3") (pintype "input"))
      (node (ref "U8") (pin "1") (pinfunction "OUT_1") (pintype "output"))
    )
    (net (code "39") (name "AREF_BUF") (class "Default")
      (node (ref "J2") (pin "1") (pinfunction "+_1") (pintype "passive"))
      (node (ref "J4") (pin "1") (pinfunction "+_1") (pintype "passive"))
      (node (ref "U13") (pin "1") (pinfunction "VOUTA_1") (pintype "output"))
      (node (ref "U13") (pin "2") (pinfunction "VINA-_2") (pintype "input"))
    )
    (net (code "40") (name "GND") (class "Default")
      (node (ref "C10") (pin "1") (pinfunction "1_1") (pintype "passive"))
      (node (ref "C11") (pin "2") (pinfunction "2_2") (pintype "passive"))
      (node (ref "C12") (pin "2") (pinfunction "2_2") (pintype "passive"))
      (node (ref "C13") (pin "2") (pinfunction "2_2") (pintype "passive"))
      (node (ref "C14") (pin "2") (pinfunction "2_2") (pintype "passive"))
      (node (ref "C15") (pin "2") (pinfunction "2_2") (pintype "passive"))
      (node (ref "C16") (pin "2") (pinfunction "2_2") (pintype "passive"))
      (node (ref "C17") (pin "2") (pinfunction "2_2") (pintype "passive"))
      (node (ref "C18") (pin "2") (pinfunction "2_2") (pintype "passive"))
      (node (ref "C19") (pin "1") (pinfunction "1_1") (pintype "passive"))
      (node (ref "C2") (pin "2") (pinfunction "2_2") (pintype "passive"))
      (node (ref "C20") (pin "2") (pinfunction "2_2") (pintype "passive"))
      (node (ref "C21") (pin "2") (pinfunction "2_2") (pintype "passive"))
      (node (ref "C22") (pin "2") (pinfunction "2_2") (pintype "passive"))
      (node (ref "C23") (pin "2") (pinfunction "2_2") (pintype "passive"))
      (node (ref "C24") (pin "1") (pinfunction "1_1") (pintype "passive"))
      (node (ref "C25") (pin "2") (pinfunction "2_2") (pintype "passive"))
      (node (ref "C26") (pin "1") (pinfunction "1_1") (pintype "passive"))
      (node (ref "C27") (pin "2") (pinfunction "2_2") (pintype "passive"))
      (node (ref "C28") (pin "2") (pinfunction "2_2") (pintype "passive"))
      (node (ref "C29") (pin "2") (pinfunction "2_2") (pintype "passive"))
      (node (ref "C3") (pin "2") (pinfunction "2_2") (pintype "passive"))
      (node (ref "C30") (pin "1") (pinfunction "1_1") (pintype "passive"))
      (node (ref "C31") (pin "2") (pinfunction "2_2") (pintype "passive"))
      (node (ref "C32") (pin "2") (pinfunction "2_2") (pintype "passive"))
      (node (ref "C33") (pin "2") (pinfunction "2_2") (pintype "passive"))
      (node (ref "C4") (pin "2") (pinfunction "2_2") (pintype "passive"))
      (node (ref "C5") (pin "2") (pinfunction "2_2") (pintype "passive"))
      (node (ref "C6") (pin "2") (pinfunction "2_2") (pintype "passive"))
      (node (ref "C7") (pin "1") (pinfunction "1_1") (pintype "passive"))
      (node (ref "C8") (pin "2") (pinfunction "2_2") (pintype "passive"))
      (node (ref "C9") (pin "1") (pinfunction "1_1") (pintype "passive"))
      (node (ref "D2") (pin "2") (pinfunction "A_2") (pintype "passive"))
      (node (ref "D3") (pin "1") (pinfunction "A_1") (pintype "passive"))
      (node (ref "D4") (pin "3") (pinfunction "3_3") (pintype "passive"))
      (node (ref "J1") (pin "3") (pinfunction "GND_3") (pintype "passive"))
      (node (ref "J1") (pin "5") (pinfunction "GND_5") (pintype "passive"))
      (node (ref "J6") (pin "2") (pinfunction "2_2") (pintype "passive"))
      (node (ref "J6") (pin "5") (pinfunction "5_5") (pintype "passive"))
      (node (ref "J6") (pin "7") (pinfunction "7_7") (pintype "passive"))
      (node (ref "J7") (pin "8") (pinfunction "8_8") (pintype "passive"))
      (node (ref "J8") (pin "4") (pinfunction "4_4") (pintype "passive"))
      (node (ref "LD2") (pin "3") (pinfunction "VSS_3") (pintype "power_in"))
      (node (ref "Q2") (pin "3") (pinfunction "S_3") (pintype "passive"))
      (node (ref "R10") (pin "2") (pinfunction "2_2") (pintype "passive"))
      (node (ref "R11") (pin "1") (pinfunction "1_1") (pintype "passive"))
      (node (ref "R13") (pin "2") (pinfunction "2_2") (pintype "passive"))
      (node (ref "R16") (pin "1") (pinfunction "1_1") (pintype "passive"))
      (node (ref "R17") (pin "2") (pinfunction "2_2") (pintype "passive"))
      (node (ref "R19") (pin "2") (pinfunction "2_2") (pintype "passive"))
      (node (ref "R21") (pin "1") (pinfunction "1_1") (pintype "passive"))
      (node (ref "R22") (pin "2") (pinfunction "2_2") (pintype "passive"))
      (node (ref "R25") (pin "1") (pinfunction "1_1") (pintype "passive"))
      (node (ref "R26") (pin "1") (pinfunction "1_1") (pintype "passive"))
      (node (ref "R3") (pin "2") (pinfunction "2_2") (pintype "passive"))
      (node (ref "R5") (pin "2") (pinfunction "2_2") (pintype "passive"))
      (node (ref "R6") (pin "2") (pinfunction "2_2") (pintype "passive"))
      (node (ref "SW1") (pin "2") (pinfunction "2_2") (pintype "passive"))
      (node (ref "U1") (pin "2") (pinfunction "GND_2") (pintype "power_in"))
      (node (ref "U10") (pin "2") (pinfunction "V-_2") (pintype "power_in"))
      (node (ref "U11") (pin "4") (pinfunction "V-_4") (pintype "passive"))
      (node (ref "U12") (pin "10") (pinfunction "GND_10") (pintype "passive"))
      (node (ref "U12") (pin "28") (pinfunction "GND_28") (pintype "passive"))
      (node (ref "U12") (pin "PAD") (pinfunction "PAD_PAD") (pintype "passive"))
      (node (ref "U13") (pin "4") (pinfunction "V-_4") (pintype "passive"))
      (node (ref "U2") (pin "6") (pinfunction "GND_6") (pintype "power_in"))
      (node (ref "U2") (pin "PAD") (pinfunction "PAD_PAD") (pintype "tri_state"))
      (node (ref "U3") (pin "5") (pinfunction "GND_5") (pintype "power_in"))
      (node (ref "U4") (pin "2") (pinfunction "GND_2") (pintype "passive"))
      (node (ref "U4") (pin "PAD") (pinfunction "PAD_PAD") (pintype "passive"))
      (node (ref "U5") (pin "2") (pinfunction "GND_2") (pintype "passive"))
      (node (ref "U5") (pin "PAD") (pinfunction "PAD_PAD") (pintype "passive"))
      (node (ref "U6") (pin "3") (pinfunction "GND_3") (pintype "passive"))
      (node (ref "U7") (pin "1") (pinfunction "Anode_(-)_1") (pintype "passive"))
      (node (ref "U8") (pin "2") (pinfunction "GND_2") (pintype "power_in"))
      (node (ref "U8") (pin "3") (pinfunction "GND_3") (pintype "power_in"))
      (node (ref "U8") (pin "5") (pinfunction "GND_5") (pintype "power_in"))
      (node (ref "U9") (pin "4") (pinfunction "V-_4") (pintype "passive"))
      (node (ref "USB1") (pin "A1") (pinfunction "GND_A1") (pintype "power_in"))
      (node (ref "USB1") (pin "A12") (pinfunction "GND_A12") (pintype "power_in"))
      (node (ref "USB1") (pin "B1") (pinfunction "GND_B1") (pintype "power_in"))
      (node (ref "USB1") (pin "B12") (pinfunction "GND_B12") (pintype "power_in"))
      (node (ref "USB1") (pin "EXT_SHLD") (pintype "passive"))
      (node (ref "USB1") (pin "INT_SHLD") (pintype "passive"))
    )
    (net (code "41") (name "GND_S") (class "Default")
      (node (ref "C34") (pin "1") (pinfunction "1_1") (pintype "passive"))
      (node (ref "U14") (pin "4") (pinfunction "VSS_4") (pintype "passive"))
    )
    (net (code "42") (name "Net-(C19-Pad2)") (class "Default")
      (node (ref "C19") (pin "2") (pinfunction "2_2") (pintype "passive"))
      (node (ref "R14") (pin "2") (pinfunction "2_2") (pintype "passive"))
    )
    (net (code "43") (name "Net-(D2-K)") (class "Default")
      (node (ref "C1") (pin "1") (pinfunction "1_1") (pintype "passive"))
      (node (ref "D2") (pin "1") (pinfunction "K_1") (pintype "passive"))
      (node (ref "L1") (pin "1") (pinfunction "1_1") (pintype "passive"))
      (node (ref "U1") (pin "6") (pinfunction "SW_6") (pintype "output"))
    )
    (net (code "44") (name "Net-(J3--)") (class "Default")
      (node (ref "J3") (pin "2") (pinfunction "-_2") (pintype "passive"))
      (node (ref "Q2") (pin "2") (pinfunction "D_2") (pintype "passive"))
    )
    (net (code "45") (name "Net-(LD1-K)") (class "Default")
      (node (ref "LD1") (pin "1") (pinfunction "K_1") (pintype "passive"))
      (node (ref "R10") (pin "1") (pinfunction "1_1") (pintype "passive"))
    )
    (net (code "46") (name "Net-(Q1-PadG)") (class "Default")
      (node (ref "Q1") (pin "G") (pinfunction "G_G") (pintype "passive"))
      (node (ref "R12") (pin "2") (pinfunction "2_2") (pintype "passive"))
      (node (ref "R13") (pin "1") (pinfunction "1_1") (pintype "passive"))
    )
    (net (code "47") (name "Net-(Q2-G)") (class "Default")
      (node (ref "Q2") (pin "1") (pinfunction "G_1") (pintype "passive"))
      (node (ref "R24") (pin "1") (pinfunction "1_1") (pintype "passive"))
      (node (ref "R25") (pin "2") (pinfunction "2_2") (pintype "passive"))
    )
    (net (code "48") (name "Net-(U1-CB)") (class "Default")
      (node (ref "C1") (pin "2") (pinfunction "2_2") (pintype "passive"))
      (node (ref "U1") (pin "1") (pinfunction "CB_1") (pintype "input"))
    )
    (net (code "49") (name "Net-(U1-FB)") (class "Default")
      (node (ref "R1") (pin "1") (pinfunction "1_1") (pintype "passive"))
      (node (ref "R3") (pin "1") (pinfunction "1_1") (pintype "passive"))
      (node (ref "U1") (pin "3") (pinfunction "FB_3") (pintype "input"))
    )
    (net (code "50") (name "Net-(U2-Y)") (class "Default")
      (node (ref "R8") (pin "2") (pinfunction "2_2") (pintype "passive"))
      (node (ref "U2") (pin "9") (pinfunction "Y_9") (pintype "bidirectional"))
    )
    (net (code "51") (name "Net-(U2-Z)") (class "Default")
      (node (ref "R7") (pin "1") (pinfunction "1_1") (pintype "passive"))
      (node (ref "U2") (pin "10") (pinfunction "Z_10") (pintype "bidirectional"))
    )
    (net (code "52") (name "Net-(U9A-VINA-)") (class "Default")
      (node (ref "R17") (pin "1") (pinfunction "1_1") (pintype "passive"))
      (node (ref "R18") (pin "1") (pinfunction "1_1") (pintype "passive"))
      (node (ref "U9") (pin "2") (pinfunction "VINA-_2") (pintype "input"))
    )
    (net (code "53") (name "Net-(U9A-VOUTA)") (class "Default")
      (node (ref "R18") (pin "2") (pinfunction "2_2") (pintype "passive"))
      (node (ref "U9") (pin "1") (pinfunction "VOUTA_1") (pintype "output"))
      (node (ref "U9") (pin "5") (pinfunction "VINB+_5") (pintype "input"))
    )
    (net (code "54") (name "Net-(U10-+IN)") (class "Default")
      (node (ref "R16") (pin "2") (pinfunction "2_2") (pintype "passive"))
      (node (ref "U10") (pin "3") (pinfunction "+IN_3") (pintype "tri_state"))
      (node (ref "U7") (pin "2") (pinfunction "Cathode_(+)_2") (pintype "passive"))
    )
    (net (code "55") (name "Net-(U10--IN)") (class "Default")
      (node (ref "R19") (pin "1") (pinfunction "1_1") (pintype "passive"))
      (node (ref "R20") (pin "1") (pinfunction "1_1") (pintype "passive"))
      (node (ref "U10") (pin "4") (pinfunction "-IN_4") (pintype "tri_state"))
    )
    (net (code "56") (name "Net-(U10-OUT)") (class "Default")
      (node (ref "R15") (pin "1") (pinfunction "1_1") (pintype "passive"))
      (node (ref "R20") (pin "2") (pinfunction "2_2") (pintype "passive"))
      (node (ref "U10") (pin "1") (pinfunction "OUT_1") (pintype "passive"))
    )
    (net (code "57") (name "Net-(U11A-VINA-)") (class "Default")
      (node (ref "R22") (pin "1") (pinfunction "1_1") (pintype "passive"))
      (node (ref "R23") (pin "1") (pinfunction "1_1") (pintype "passive"))
      (node (ref "U11") (pin "2") (pinfunction "VINA-_2") (pintype "input"))
    )
    (net (code "58") (name "Net-(U11A-VOUTA)") (class "Default")
      (node (ref "R23") (pin "2") (pinfunction "2_2") (pintype "passive"))
      (node (ref "U11") (pin "1") (pinfunction "VOUTA_1") (pintype "output"))
      (node (ref "U11") (pin "5") (pinfunction "VINB+_5") (pintype "input"))
    )
    (net (code "59") (name "Net-(U12-VDD_CORE)") (class "Default")
      (node (ref "C33") (pin "1") (pinfunction "1_1") (pintype "passive"))
      (node (ref "U12") (pin "29") (pinfunction "VDD_CORE_29") (pintype "passive"))
    )
    (net (code "60") (name "Net-(U12-XIN32{slash}PA00)") (class "Default")
      (node (ref "C26") (pin "2") (pinfunction "2_2") (pintype "passive"))
      (node (ref "U12") (pin "1") (pinfunction "XIN32/PA00_1") (pintype "passive"))
      (node (ref "X1") (pin "1") (pinfunction "OSC1_1") (pintype "passive"))
    )
    (net (code "61") (name "Net-(U12-XOUT32{slash}PA01)") (class "Default")
      (node (ref "C25") (pin "1") (pinfunction "1_1") (pintype "passive"))
      (node (ref "U12") (pin "2") (pinfunction "XOUT32/PA01_2") (pintype "passive"))
      (node (ref "X1") (pin "2") (pinfunction "OSC2_2") (pintype "passive"))
    )
    (net (code "62") (name "Net-(USB1-CC1)") (class "Default")
      (node (ref "R5") (pin "1") (pinfunction "1_1") (pintype "passive"))
      (node (ref "USB1") (pin "A5") (pinfunction "CC1_A5") (pintype "passive"))
    )
    (net (code "63") (name "Net-(USB1-CC2)") (class "Default")
      (node (ref "R6") (pin "1") (pinfunction "1_1") (pintype "passive"))
      (node (ref "USB1") (pin "B5") (pinfunction "CC2_B5") (pintype "passive"))
    )
    (net (code "64") (name "VBUS") (class "Default")
      (node (ref "D1") (pin "2") (pinfunction "A_2") (pintype "passive"))
      (node (ref "USB1") (pin "A4") (pinfunction "Vbus_A4") (pintype "power_in"))
      (node (ref "USB1") (pin "A9") (pinfunction "Vbus_A9") (pintype "power_in"))
      (node (ref "USB1") (pin "B4") (pinfunction "Vbus_B4") (pintype "power_in"))
      (node (ref "USB1") (pin "B9") (pinfunction "Vbus_B9") (pintype "power_in"))
    )
    (net (code "65") (name "unconnected-(J1-NC-Pad6)") (class "Default")
      (node (ref "J1") (pin "6") (pinfunction "NC_6") (pintype "passive"))
    )
    (net (code "66") (name "unconnected-(J1-NC-Pad7)") (class "Default")
      (node (ref "J1") (pin "7") (pinfunction "NC_7") (pintype "passive"))
    )
    (net (code "67") (name "unconnected-(J1-NC-Pad8)") (class "Default")
      (node (ref "J1") (pin "8") (pinfunction "NC_8") (pintype "passive"))
    )
    (net (code "68") (name "unconnected-(J1-NC-Pad9)") (class "Default")
      (node (ref "J1") (pin "9") (pinfunction "NC_9") (pintype "passive"))
    )
    (net (code "69") (name "unconnected-(LD2-DOUT-Pad2)") (class "Default")
      (node (ref "LD2") (pin "2") (pinfunction "DOUT_2") (pintype "output"))
    )
    (net (code "70") (name "unconnected-(U1-~{SHDN}-Pad4)") (class "Default")
      (node (ref "U1") (pin "4") (pinfunction "~{SHDN}_4") (pintype "input"))
    )
    (net (code "71") (name "unconnected-(U2-A-Pad12)") (class "Default")
      (node (ref "U2") (pin "12") (pinfunction "A_12") (pintype "input"))
    )
    (net (code "72") (name "unconnected-(U2-B-Pad11)") (class "Default")
      (node (ref "U2") (pin "11") (pinfunction "B_11") (pintype "input"))
    )
    (net (code "73") (name "unconnected-(U2-NC-Pad16)") (class "Default")
      (node (ref "U2") (pin "16") (pinfunction "NC_16") (pintype "passive"))
    )
    (net (code "74") (name "unconnected-(U3-I{slash}O_3-Pad4)") (class "Default")
      (node (ref "U3") (pin "4") (pinfunction "I/O_3_4") (pintype "power_in"))
    )
    (net (code "75") (name "unconnected-(U3-I{slash}O_4-Pad6)") (class "Default")
      (node (ref "U3") (pin "6") (pinfunction "I/O_4_6") (pintype "power_in"))
    )
    (net (code "76") (name "unconnected-(U6-PAD-Pad6)") (class "Default")
      (node (ref "U6") (pin "6") (pinfunction "PAD_6") (pintype "passive"))
    )
    (net (code "77") (name "unconnected-(USB1-RX1+-PadB11)") (class "Default")
      (node (ref "USB1") (pin "B11") (pinfunction "RX1+_B11") (pintype "input"))
    )
    (net (code "78") (name "unconnected-(USB1-RX1--PadB10)") (class "Default")
      (node (ref "USB1") (pin "B10") (pinfunction "RX1-_B10") (pintype "input"))
    )
    (net (code "79") (name "unconnected-(USB1-RX2+-PadA11)") (class "Default")
      (node (ref "USB1") (pin "A11") (pinfunction "RX2+_A11") (pintype "input"))
    )
    (net (code "80") (name "unconnected-(USB1-RX2--PadA10)") (class "Default")
      (node (ref "USB1") (pin "A10") (pinfunction "RX2-_A10") (pintype "input"))
    )
    (net (code "81") (name "unconnected-(USB1-SBU1-PadA8)") (class "Default")
      (node (ref "USB1") (pin "A8") (pinfunction "SBU1_A8") (pintype "passive"))
    )
    (net (code "82") (name "unconnected-(USB1-SBU2-PadB8)") (class "Default")
      (node (ref "USB1") (pin "B8") (pinfunction "SBU2_B8") (pintype "passive"))
    )
    (net (code "83") (name "unconnected-(USB1-TX1+-PadA2)") (class "Default")
      (node (ref "USB1") (pin "A2") (pinfunction "TX1+_A2") (pintype "output"))
    )
    (net (code "84") (name "unconnected-(USB1-TX1--PadA3)") (class "Default")
      (node (ref "USB1") (pin "A3") (pinfunction "TX1-_A3") (pintype "output"))
    )
    (net (code "85") (name "unconnected-(USB1-TX2+-PadB2)") (class "Default")
      (node (ref "USB1") (pin "B2") (pinfunction "TX2+_B2") (pintype "output"))
    )
    (net (code "86") (name "unconnected-(USB1-TX2--PadB3)") (class "Default")
      (node (ref "USB1") (pin "B3") (pinfunction "TX2-_B3") (pintype "output"))
    )
  )
)
